# CC2530_ADXL345.net
KiCad netlist of a schematic drawn in Altium Designer
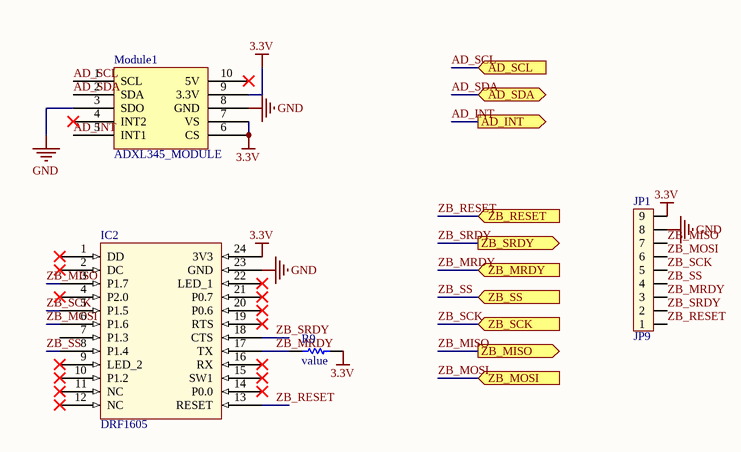
[diagram p0: CC2530_ADXL345.SchDoc]

(export (version "E")
  (design (tool "Eeschema 10.0.6"))
  (components
    (comp (ref "IC2")
      (value "DRF1605")
      (footprint "DRF1605")
      (libsource (lib "HoangViet_AltiumLib") (part "DRF1605"))
    )
    (comp (ref "JP1") (value "JP9") (footprint "JP9") (libsource (lib "linhien69") (part "JP9")))
    (comp (ref "Module1")
      (value "ADXL345_MODULE")
      (footprint "ADXL345_MODULE")
      (libsource (lib "HoangViet_AltiumLib") (part "ADXL345_MODULE"))
    )
    (comp (ref "R9")
      (value "value")
      (footprint "RES 0805")
      (description "resistor smd0805")
      (libsource (lib "HoangViet_AltiumLib") (part "Res_0805"))
    )
  )
  (nets
    (net (code "1") (name "/AD_INT") (class "Default")
      (node (ref "Module1") (pin "5") (pinfunction "INT1_5") (pintype "passive"))
    )
    (net (code "2") (name "/AD_SCL") (class "Default")
      (node (ref "Module1") (pin "1") (pinfunction "SCL_1") (pintype "passive"))
    )
    (net (code "3") (name "/AD_SDA") (class "Default")
      (node (ref "Module1") (pin "2") (pinfunction "SDA_2") (pintype "passive"))
    )
    (net (code "4") (name "/ZB_MISO") (class "Default")
      (node (ref "IC2") (pin "3") (pinfunction "P1.7_3") (pintype "input"))
      (node (ref "JP1") (pin "7") (pinfunction "7_7") (pintype "passive"))
    )
    (net (code "5") (name "/ZB_MOSI") (class "Default")
      (node (ref "IC2") (pin "6") (pinfunction "P1.6_6") (pintype "input"))
      (node (ref "JP1") (pin "6") (pinfunction "6_6") (pintype "passive"))
    )
    (net (code "6") (name "/ZB_MRDY") (class "Default")
      (node (ref "IC2") (pin "17") (pinfunction "TX_17") (pintype "input"))
      (node (ref "JP1") (pin "3") (pinfunction "3_3") (pintype "passive"))
      (node (ref "R9") (pin "2") (pinfunction "2_2") (pintype "passive"))
    )
    (net (code "7") (name "/ZB_RESET") (class "Default")
      (node (ref "IC2") (pin "13") (pinfunction "RESET_13") (pintype "input"))
      (node (ref "JP1") (pin "1") (pinfunction "1_1") (pintype "passive"))
    )
    (net (code "8") (name "/ZB_SCK") (class "Default")
      (node (ref "IC2") (pin "5") (pinfunction "P1.5_5") (pintype "input"))
      (node (ref "JP1") (pin "5") (pinfunction "5_5") (pintype "passive"))
    )
    (net (code "9") (name "/ZB_SRDY") (class "Default")
      (node (ref "IC2") (pin "18") (pinfunction "CTS_18") (pintype "input"))
      (node (ref "JP1") (pin "2") (pinfunction "2_2") (pintype "passive"))
    )
    (net (code "10") (name "/ZB_SS") (class "Default")
      (node (ref "IC2") (pin "8") (pinfunction "P1.4_8") (pintype "input"))
      (node (ref "JP1") (pin "4") (pinfunction "4_4") (pintype "passive"))
    )
    (net (code "11") (name "3.3V") (class "Default")
      (node (ref "IC2") (pin "24") (pinfunction "3V3_24") (pintype "input"))
      (node (ref "JP1") (pin "9") (pinfunction "9_9") (pintype "passive"))
      (node (ref "Module1") (pin "6") (pinfunction "CS_6") (pintype "passive"))
      (node (ref "Module1") (pin "7") (pinfunction "VS_7") (pintype "passive"))
      (node (ref "Module1") (pin "9") (pinfunction "3.3V_9") (pintype "passive"))
      (node (ref "R9") (pin "1") (pinfunction "1_1") (pintype "passive"))
    )
    (net (code "12") (name "GND") (class "Default")
      (node (ref "IC2") (pin "23") (pinfunction "GND_23") (pintype "input"))
      (node (ref "JP1") (pin "8") (pinfunction "8_8") (pintype "passive"))
      (node (ref "Module1") (pin "3") (pinfunction "SDO_3") (pintype "passive"))
      (node (ref "Module1") (pin "8") (pinfunction "GND_8") (pintype "passive"))
    )
    (net (code "13") (name "unconnected-(IC2-DC-Pad2)") (class "Default")
      (node (ref "IC2") (pin "2") (pinfunction "DC_2") (pintype "input+no_connect"))
    )
    (net (code "14") (name "unconnected-(IC2-DD-Pad1)") (class "Default")
      (node (ref "IC2") (pin "1") (pinfunction "DD_1") (pintype "input+no_connect"))
    )
    (net (code "15") (name "unconnected-(IC2-LED_1-Pad22)") (class "Default")
      (node (ref "IC2") (pin "22") (pinfunction "LED_1_22") (pintype "input+no_connect"))
    )
    (net (code "16") (name "unconnected-(IC2-LED_2-Pad9)") (class "Default")
      (node (ref "IC2") (pin "9") (pinfunction "LED_2_9") (pintype "input+no_connect"))
    )
    (net (code "17") (name "unconnected-(IC2-NC-Pad11)") (class "Default")
      (node (ref "IC2") (pin "11") (pinfunction "NC_11") (pintype "input+no_connect"))
    )
    (net (code "18") (name "unconnected-(IC2-NC-Pad12)") (class "Default")
      (node (ref "IC2") (pin "12") (pinfunction "NC_12") (pintype "input+no_connect"))
    )
    (net (code "19") (name "unconnected-(IC2-P0.0-Pad14)") (class "Default")
      (node (ref "IC2") (pin "14") (pinfunction "P0.0_14") (pintype "input+no_connect"))
    )
    (net (code "20") (name "unconnected-(IC2-P0.6-Pad20)") (class "Default")
      (node (ref "IC2") (pin "20") (pinfunction "P0.6_20") (pintype "input+no_connect"))
    )
    (net (code "21") (name "unconnected-(IC2-P0.7-Pad21)") (class "Default")
      (node (ref "IC2") (pin "21") (pinfunction "P0.7_21") (pintype "input+no_connect"))
    )
    (net (code "22") (name "unconnected-(IC2-P1.2-Pad10)") (class "Default")
      (node (ref "IC2") (pin "10") (pinfunction "P1.2_10") (pintype "input+no_connect"))
    )
    (net (code "23") (name "unconnected-(IC2-P1.3-Pad7)") (class "Default")
      (node (ref "IC2") (pin "7") (pinfunction "P1.3_7") (pintype "input"))
    )
    (net (code "24") (name "unconnected-(IC2-P2.0-Pad4)") (class "Default")
      (node (ref "IC2") (pin "4") (pinfunction "P2.0_4") (pintype "input+no_connect"))
    )
    (net (code "25") (name "unconnected-(IC2-RTS-Pad19)") (class "Default")
      (node (ref "IC2") (pin "19") (pinfunction "RTS_19") (pintype "input+no_connect"))
    )
    (net (code "26") (name "unconnected-(IC2-RX-Pad16)") (class "Default")
      (node (ref "IC2") (pin "16") (pinfunction "RX_16") (pintype "input+no_connect"))
    )
    (net (code "27") (name "unconnected-(IC2-SW1-Pad15)") (class "Default")
      (node (ref "IC2") (pin "15") (pinfunction "SW1_15") (pintype "input+no_connect"))
    )
    (net (code "28") (name "unconnected-(Module1-5V-Pad10)") (class "Default")
      (node (ref "Module1") (pin "10") (pinfunction "5V_10") (pintype "passive+no_connect"))
    )
    (net (code "29") (name "unconnected-(Module1-INT2-Pad4)") (class "Default")
      (node (ref "Module1") (pin "4") (pinfunction "INT2_4") (pintype "passive+no_connect"))
    )
  )
)
